# ELRS.net
KiCad netlist of a schematic drawn in Altium Designer
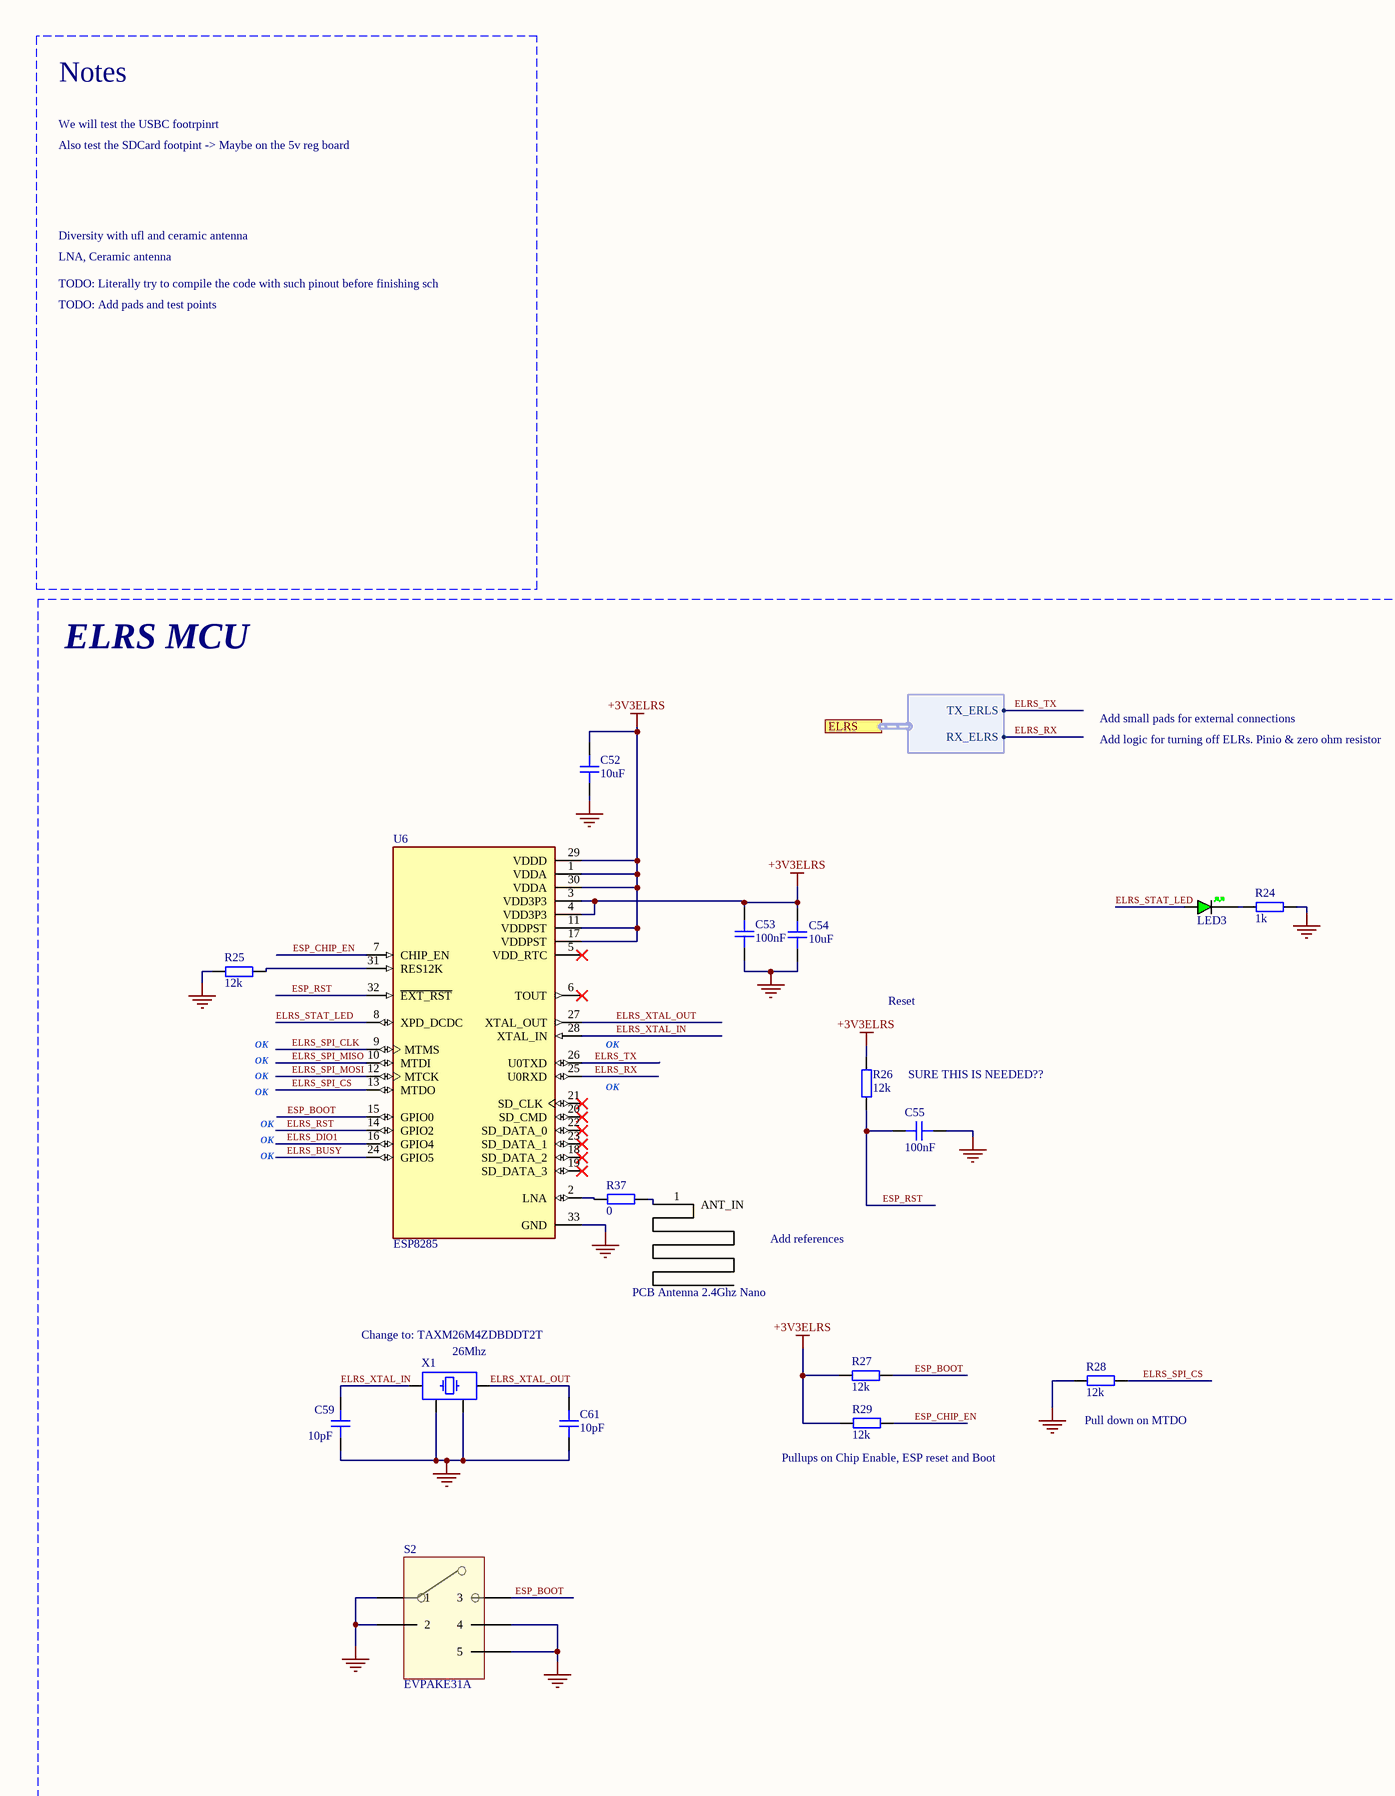
[diagram p0: ELRS.SchDoc, left]
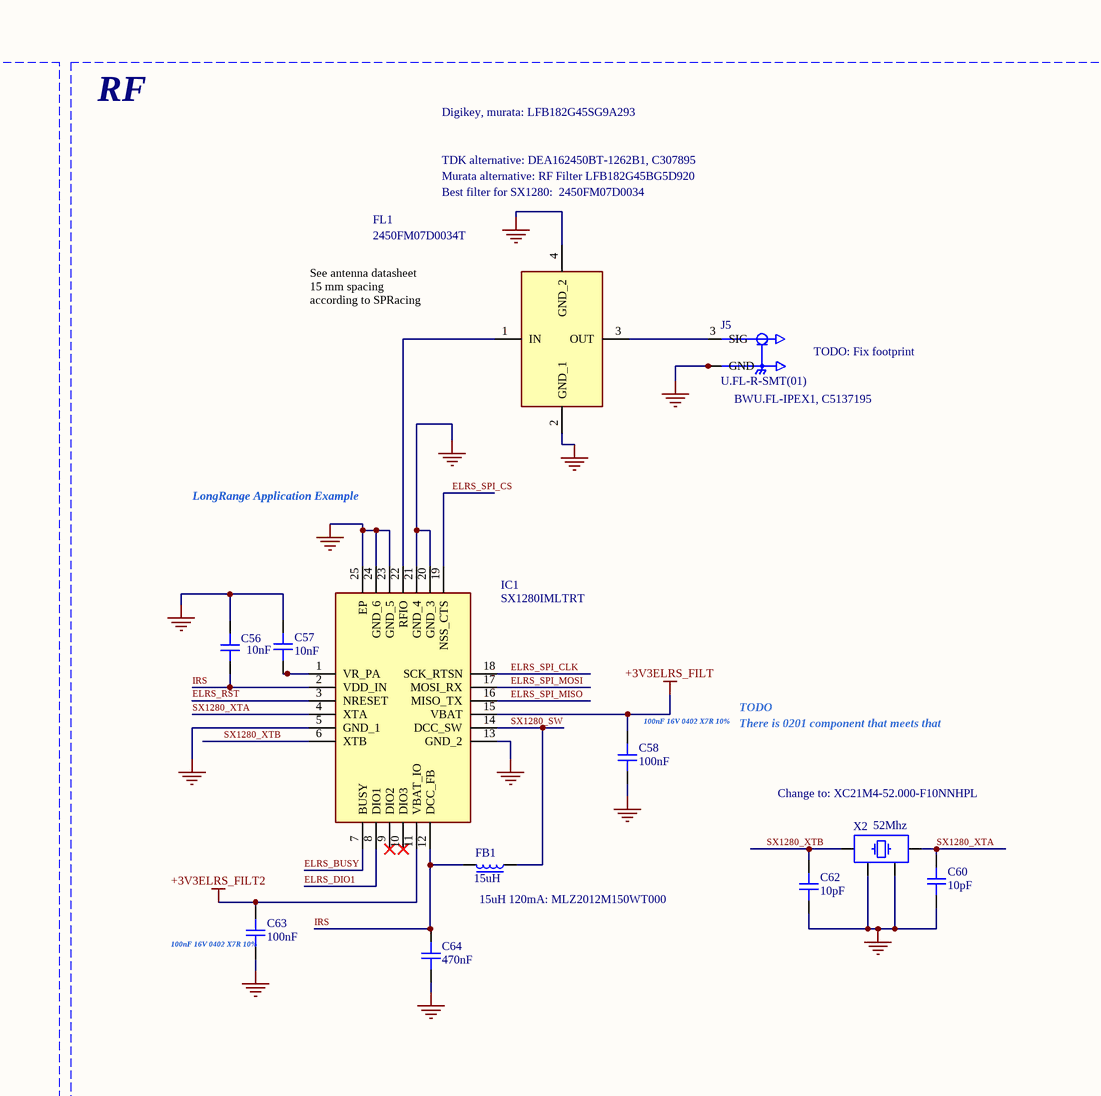
[diagram p1: ELRS.SchDoc, right]

(export (version "E")
  (design (tool "Eeschema 10.0.6"))
  (components
    (comp (ref "C52")
      (value "10uF")
      (footprint "CAP_0402")
      (description "Capacitor SMD 0402")
      (libsource (lib "Schematic-Lib-PhilsLab") (part "CAP_0402"))
    )
    (comp (ref "C53")
      (value "100nF")
      (footprint "CAP_0201")
      (description "Capacitor SMD 0201")
      (libsource (lib "Schematic-Lib-PhilsLab") (part "CAP_0201"))
    )
    (comp (ref "C54")
      (value "10uF")
      (footprint "CAP_0402")
      (description "Capacitor SMD 0402")
      (libsource (lib "Schematic-Lib-PhilsLab") (part "CAP_0402"))
    )
    (comp (ref "C55")
      (value "100nF")
      (footprint "CAP_0201")
      (description "Capacitor SMD 0201")
      (libsource (lib "Schematic-Lib-PhilsLab") (part "CAP_0201"))
    )
    (comp (ref "C56")
      (value "10nF")
      (footprint "CAP_0201")
      (description "Capacitor SMD 0201")
      (libsource (lib "Schematic-Lib-PhilsLab") (part "CAP_0201"))
    )
    (comp (ref "C57")
      (value "10nF")
      (footprint "CAP_0201")
      (description "Capacitor SMD 0201")
      (libsource (lib "Schematic-Lib-PhilsLab") (part "CAP_0201"))
    )
    (comp (ref "C58")
      (value "100nF")
      (footprint "CAP_0201")
      (description "Capacitor SMD 0201")
      (libsource (lib "Schematic-Lib-PhilsLab") (part "CAP_0201"))
    )
    (comp (ref "C59")
      (value "10pF")
      (footprint "CAP_0201")
      (description "Capacitor SMD 0201")
      (libsource (lib "Schematic-Lib-PhilsLab") (part "CAP_0201"))
    )
    (comp (ref "C60")
      (value "10pF")
      (footprint "CAP_0201")
      (description "Capacitor SMD 0201")
      (libsource (lib "Schematic-Lib-PhilsLab") (part "CAP_0201"))
    )
    (comp (ref "C61")
      (value "10pF")
      (footprint "CAP_0201")
      (description "Capacitor SMD 0201")
      (libsource (lib "Schematic-Lib-PhilsLab") (part "CAP_0201"))
    )
    (comp (ref "C62")
      (value "10pF")
      (footprint "CAP_0201")
      (description "Capacitor SMD 0201")
      (libsource (lib "Schematic-Lib-PhilsLab") (part "CAP_0201"))
    )
    (comp (ref "C63")
      (value "100nF")
      (footprint "CAP_0201")
      (description "Capacitor SMD 0201")
      (libsource (lib "Schematic-Lib-PhilsLab") (part "CAP_0201"))
    )
    (comp (ref "C64")
      (value "470nF")
      (footprint "CAP_0402")
      (description "Capacitor SMD 0402")
      (libsource (lib "Schematic-Lib-PhilsLab") (part "CAP_0402"))
    )
    (comp (ref "FB1")
      (value "15uH")
      (footprint "FB_0805")
      (description "Ferrite Bead SMD 0805")
      (libsource (lib "Schematic-Lib-PhilsLab") (part "FB_0805"))
    )
    (comp (ref "FL1")
      (value "2450FM07D0034T")
      (footprint "SamacSys:2450FM07D0034T")
      (description "Filter")
      (fields (field (name "MOUSER PART NUMBER") "609-2450FM07D0034T"))
      (libsource (lib "*") (part "2450FM07D0034T"))
    )
    (comp (ref "IC1")
      (value "SX1280IMLTRT")
      (footprint "SamacSys:QFN50P400X400X100-25N-D")
      (description "Integrated Circuit")
      (fields (field (name "MOUSER PART NUMBER") "947-SX1280IMLTRT"))
      (libsource (lib "*") (part "SX1280IMLTRT"))
    )
    (comp (ref "J5")
      (value "U.FL-R-SMT(01)")
      (footprint "HRS_U.FL-R-SMT(01)")
      (fields (field (name "MF") "Hirose"))
      (libsource (lib "Schematic-Lib-Singu") (part "U.FL-R-SMT(01)"))
    )
    (comp (ref "LED3")
      (value "GREEN")
      (footprint "LED_0402_GREEN")
      (description "LED 0402 GREEN SMD")
      (libsource (lib "Schematic-Lib-PhilsLab") (part "LED_0402_GREEN"))
    )
    (comp (ref "PCNANT1")
      (value "PCB Antenna 2.4Ghz Nano")
      (footprint "PCB Antena Micro 2.4Ghz")
      (libsource (lib "Schematic-Lib-Singu") (part "PCB Antenna 2.4Ghz Nano"))
    )
    (comp (ref "R24")
      (value "1k")
      (footprint "RES_0201")
      (description "Resistor SMD 0201")
      (libsource (lib "Schematic-Lib-PhilsLab") (part "RES_0201"))
    )
    (comp (ref "R25")
      (value "12k")
      (footprint "RES_0201")
      (description "Resistor SMD 0201")
      (libsource (lib "Schematic-Lib-PhilsLab") (part "RES_0201"))
    )
    (comp (ref "R26")
      (value "12k")
      (footprint "RES_0201")
      (description "Resistor SMD 0201")
      (libsource (lib "Schematic-Lib-PhilsLab") (part "RES_0201"))
    )
    (comp (ref "R27")
      (value "12k")
      (footprint "RES_0201")
      (description "Resistor SMD 0201")
      (libsource (lib "Schematic-Lib-PhilsLab") (part "RES_0201"))
    )
    (comp (ref "R28")
      (value "12k")
      (footprint "RES_0201")
      (description "Resistor SMD 0201")
      (libsource (lib "Schematic-Lib-PhilsLab") (part "RES_0201"))
    )
    (comp (ref "R29")
      (value "12k")
      (footprint "RES_0201")
      (description "Resistor SMD 0201")
      (libsource (lib "Schematic-Lib-PhilsLab") (part "RES_0201"))
    )
    (comp (ref "R37")
      (value "0")
      (footprint "RES_0402")
      (description "Resistor SMD 0402")
      (libsource (lib "Schematic-Lib-PhilsLab") (part "RES_0402"))
    )
    (comp (ref "S2")
      (value "EVPAKE31A")
      (footprint "EVPAKE31A")
      (libsource (lib "Schematic-Lib-Singu") (part "EVPAKE31A"))
    )
    (comp (ref "U6")
      (value "ESP8285")
      (footprint "QFN50P500X500X90-33N")
      (description "IC RF TxRx + MCU WiFi 802.11b/g/n 2.4GHz 32-VFQFN Exposed Pad")
      (fields (field (name "MF") "Espressif Systems"))
      (libsource (lib "Schematic-Lib-Singu") (part "ESP8285"))
    )
    (comp (ref "X1")
      (value "26Mhz")
      (footprint "XTAL_2016")
      (description "Crystal SMD 4-Pin 2.0x1.6mm")
      (libsource (lib "Schematic-Lib-PhilsLab") (part "XTAL_2016"))
    )
    (comp (ref "X2")
      (value "52Mhz")
      (footprint "XTAL_2016")
      (description "Crystal SMD 4-Pin 2.0x1.6mm")
      (libsource (lib "Schematic-Lib-PhilsLab") (part "XTAL_2016"))
    )
  )
  (nets
    (net (code "2") (name "+3V3ELRS") (class "Default")
      (node (ref "C52") (pin "2") (pinfunction "2_2") (pintype "passive"))
      (node (ref "C53") (pin "2") (pinfunction "2_2") (pintype "passive"))
      (node (ref "C54") (pin "2") (pinfunction "2_2") (pintype "passive"))
      (node (ref "R26") (pin "2") (pinfunction "2_2") (pintype "passive"))
      (node (ref "R27") (pin "1") (pinfunction "1_1") (pintype "passive"))
      (node (ref "R29") (pin "1") (pinfunction "1_1") (pintype "passive"))
      (node (ref "U6") (pin "1") (pinfunction "VDDA_1") (pintype "power_in"))
      (node (ref "U6") (pin "11") (pinfunction "VDDPST_11") (pintype "power_in"))
      (node (ref "U6") (pin "17") (pinfunction "VDDPST_17") (pintype "power_in"))
      (node (ref "U6") (pin "29") (pinfunction "VDDD_29") (pintype "power_in"))
      (node (ref "U6") (pin "3") (pinfunction "VDD3P3_3") (pintype "power_in"))
      (node (ref "U6") (pin "30") (pinfunction "VDDA_30") (pintype "power_in"))
      (node (ref "U6") (pin "4") (pinfunction "VDD3P3_4") (pintype "power_in"))
    )
    (net (code "3") (name "+3V3ELRS_FILT") (class "Default")
      (node (ref "C58") (pin "2") (pinfunction "2_2") (pintype "passive"))
      (node (ref "IC1") (pin "15") (pinfunction "VBAT_15") (pintype "passive"))
    )
    (net (code "4") (name "+3V3ELRS_FILT2") (class "Default")
      (node (ref "C63") (pin "2") (pinfunction "2_2") (pintype "passive"))
      (node (ref "IC1") (pin "11") (pinfunction "VBAT_IO_11") (pintype "passive"))
    )
    (net (code "5") (name "/ELRS_BUSY") (class "Default")
      (node (ref "IC1") (pin "7") (pinfunction "BUSY_7") (pintype "passive"))
      (node (ref "U6") (pin "24") (pinfunction "GPIO5_24") (pintype "bidirectional"))
    )
    (net (code "6") (name "/ELRS_DIO1") (class "Default")
      (node (ref "IC1") (pin "8") (pinfunction "DIO1_8") (pintype "passive"))
      (node (ref "U6") (pin "16") (pinfunction "GPIO4_16") (pintype "bidirectional"))
    )
    (net (code "7") (name "/ELRS_RST") (class "Default")
      (node (ref "IC1") (pin "3") (pinfunction "NRESET_3") (pintype "passive"))
      (node (ref "U6") (pin "14") (pinfunction "GPIO2_14") (pintype "bidirectional"))
    )
    (net (code "8") (name "/ELRS_RX") (class "Default")
      (node (ref "U6") (pin "25") (pinfunction "U0RXD_25") (pintype "bidirectional"))
    )
    (net (code "9") (name "/ELRS_SPI_CLK") (class "Default")
      (node (ref "IC1") (pin "18") (pinfunction "SCK_RTSN_18") (pintype "passive"))
      (node (ref "U6") (pin "9") (pinfunction "MTMS_9") (pintype "bidirectional"))
    )
    (net (code "10") (name "/ELRS_SPI_CS") (class "Default")
      (node (ref "IC1") (pin "19") (pinfunction "NSS_CTS_19") (pintype "passive"))
      (node (ref "R28") (pin "2") (pinfunction "2_2") (pintype "passive"))
      (node (ref "U6") (pin "13") (pinfunction "MTDO_13") (pintype "bidirectional"))
    )
    (net (code "11") (name "/ELRS_SPI_MISO") (class "Default")
      (node (ref "IC1") (pin "16") (pinfunction "MISO_TX_16") (pintype "passive"))
      (node (ref "U6") (pin "10") (pinfunction "MTDI_10") (pintype "bidirectional"))
    )
    (net (code "12") (name "/ELRS_SPI_MOSI") (class "Default")
      (node (ref "IC1") (pin "17") (pinfunction "MOSI_RX_17") (pintype "passive"))
      (node (ref "U6") (pin "12") (pinfunction "MTCK_12") (pintype "bidirectional"))
    )
    (net (code "13") (name "/ELRS_STAT_LED") (class "Default")
      (node (ref "LED3") (pin "A") (pinfunction "A_A") (pintype "passive"))
      (node (ref "U6") (pin "8") (pinfunction "XPD_DCDC_8") (pintype "bidirectional"))
    )
    (net (code "14") (name "/ELRS_TX") (class "Default")
      (node (ref "U6") (pin "26") (pinfunction "U0TXD_26") (pintype "bidirectional"))
    )
    (net (code "15") (name "/ELRS_XTAL_IN") (class "Default")
      (node (ref "C59") (pin "2") (pinfunction "2_2") (pintype "passive"))
      (node (ref "U6") (pin "28") (pinfunction "XTAL_IN_28") (pintype "input"))
      (node (ref "X1") (pin "1") (pinfunction "1_1") (pintype "passive"))
    )
    (net (code "16") (name "/ELRS_XTAL_OUT") (class "Default")
      (node (ref "C61") (pin "2") (pinfunction "2_2") (pintype "passive"))
      (node (ref "U6") (pin "27") (pinfunction "XTAL_OUT_27") (pintype "output"))
      (node (ref "X1") (pin "3") (pinfunction "3_3") (pintype "passive"))
    )
    (net (code "17") (name "/ESP_BOOT") (class "Default")
      (node (ref "R27") (pin "2") (pinfunction "2_2") (pintype "passive"))
      (node (ref "S2") (pin "3") (pinfunction "3_3") (pintype "passive"))
      (node (ref "U6") (pin "15") (pinfunction "GPIO0_15") (pintype "bidirectional"))
    )
    (net (code "18") (name "/ESP_CHIP_EN") (class "Default")
      (node (ref "R29") (pin "2") (pinfunction "2_2") (pintype "passive"))
      (node (ref "U6") (pin "7") (pinfunction "CHIP_EN_7") (pintype "input"))
    )
    (net (code "19") (name "/ESP_RST") (class "Default")
      (node (ref "C55") (pin "2") (pinfunction "2_2") (pintype "passive"))
      (node (ref "R26") (pin "1") (pinfunction "1_1") (pintype "passive"))
      (node (ref "U6") (pin "32") (pinfunction "~{EXT_RST}_32") (pintype "input"))
    )
    (net (code "20") (name "/IRS") (class "Default")
      (node (ref "C56") (pin "1") (pinfunction "1_1") (pintype "passive"))
      (node (ref "C64") (pin "1") (pinfunction "1_1") (pintype "passive"))
      (node (ref "FB1") (pin "2") (pinfunction "2_2") (pintype "passive"))
      (node (ref "IC1") (pin "12") (pinfunction "DCC_FB_12") (pintype "passive"))
      (node (ref "IC1") (pin "2") (pinfunction "VDD_IN_2") (pintype "passive"))
    )
    (net (code "21") (name "/SX1280_SW") (class "Default")
      (node (ref "FB1") (pin "1") (pinfunction "1_1") (pintype "passive"))
      (node (ref "IC1") (pin "14") (pinfunction "DCC_SW_14") (pintype "passive"))
    )
    (net (code "22") (name "/SX1280_XTA") (class "Default")
      (node (ref "C60") (pin "2") (pinfunction "2_2") (pintype "passive"))
      (node (ref "IC1") (pin "4") (pinfunction "XTA_4") (pintype "passive"))
      (node (ref "X2") (pin "3") (pinfunction "3_3") (pintype "passive"))
    )
    (net (code "23") (name "/SX1280_XTB") (class "Default")
      (node (ref "C62") (pin "2") (pinfunction "2_2") (pintype "passive"))
      (node (ref "IC1") (pin "6") (pinfunction "XTB_6") (pintype "passive"))
      (node (ref "X2") (pin "1") (pinfunction "1_1") (pintype "passive"))
    )
    (net (code "25") (name "GND") (class "Default")
      (node (ref "C52") (pin "1") (pinfunction "1_1") (pintype "passive"))
      (node (ref "C53") (pin "1") (pinfunction "1_1") (pintype "passive"))
      (node (ref "C54") (pin "1") (pinfunction "1_1") (pintype "passive"))
      (node (ref "C55") (pin "1") (pinfunction "1_1") (pintype "passive"))
      (node (ref "C56") (pin "2") (pinfunction "2_2") (pintype "passive"))
      (node (ref "C57") (pin "2") (pinfunction "2_2") (pintype "passive"))
      (node (ref "C58") (pin "1") (pinfunction "1_1") (pintype "passive"))
      (node (ref "C59") (pin "1") (pinfunction "1_1") (pintype "passive"))
      (node (ref "C60") (pin "1") (pinfunction "1_1") (pintype "passive"))
      (node (ref "C61") (pin "1") (pinfunction "1_1") (pintype "passive"))
      (node (ref "C62") (pin "1") (pinfunction "1_1") (pintype "passive"))
      (node (ref "C63") (pin "1") (pinfunction "1_1") (pintype "passive"))
      (node (ref "C64") (pin "2") (pinfunction "2_2") (pintype "passive"))
      (node (ref "FL1") (pin "2") (pinfunction "GND_1_2") (pintype "passive"))
      (node (ref "FL1") (pin "4") (pinfunction "GND_2_4") (pintype "passive"))
      (node (ref "IC1") (pin "13") (pinfunction "GND_2_13") (pintype "passive"))
      (node (ref "IC1") (pin "20") (pinfunction "GND_3_20") (pintype "passive"))
      (node (ref "IC1") (pin "21") (pinfunction "GND_4_21") (pintype "passive"))
      (node (ref "IC1") (pin "23") (pinfunction "GND_5_23") (pintype "passive"))
      (node (ref "IC1") (pin "24") (pinfunction "GND_6_24") (pintype "passive"))
      (node (ref "IC1") (pin "25") (pinfunction "EP_25") (pintype "passive"))
      (node (ref "IC1") (pin "5") (pinfunction "GND_1_5") (pintype "passive"))
      (node (ref "J5") (pin "1") (pinfunction "GND_1") (pintype "passive"))
      (node (ref "J5") (pin "2") (pinfunction "GND_2") (pintype "passive"))
      (node (ref "R24") (pin "2") (pinfunction "2_2") (pintype "passive"))
      (node (ref "R25") (pin "1") (pinfunction "1_1") (pintype "passive"))
      (node (ref "R28") (pin "1") (pinfunction "1_1") (pintype "passive"))
      (node (ref "S2") (pin "1") (pinfunction "1_1") (pintype "passive"))
      (node (ref "S2") (pin "2") (pinfunction "2_2") (pintype "passive"))
      (node (ref "S2") (pin "4") (pinfunction "4_4") (pintype "passive"))
      (node (ref "S2") (pin "5") (pinfunction "5_5") (pintype "passive"))
      (node (ref "U6") (pin "33") (pinfunction "GND_33") (pintype "power_in"))
      (node (ref "X1") (pin "2") (pinfunction "2_2") (pintype "passive"))
      (node (ref "X1") (pin "4") (pinfunction "4_4") (pintype "passive"))
      (node (ref "X2") (pin "2") (pinfunction "2_2") (pintype "passive"))
      (node (ref "X2") (pin "4") (pinfunction "4_4") (pintype "passive"))
    )
    (net (code "26") (name "Net-(FL1-IN)") (class "Default")
      (node (ref "FL1") (pin "1") (pinfunction "IN_1") (pintype "passive"))
      (node (ref "IC1") (pin "22") (pinfunction "RFIO_22") (pintype "passive"))
    )
    (net (code "27") (name "Net-(FL1-OUT)") (class "Default")
      (node (ref "FL1") (pin "3") (pinfunction "OUT_3") (pintype "passive"))
      (node (ref "J5") (pin "3") (pinfunction "SIG_3") (pintype "passive"))
    )
    (net (code "28") (name "Net-(IC1-VR_PA)") (class "Default")
      (node (ref "C57") (pin "1") (pinfunction "1_1") (pintype "passive"))
      (node (ref "IC1") (pin "1") (pinfunction "VR_PA_1") (pintype "passive"))
    )
    (net (code "29") (name "Net-(LED3-PadK)") (class "Default")
      (node (ref "LED3") (pin "K") (pinfunction "K_K") (pintype "passive"))
      (node (ref "R24") (pin "1") (pinfunction "1_1") (pintype "passive"))
    )
    (net (code "30") (name "Net-(PCNANT1-ANT_IN)") (class "Default")
      (node (ref "PCNANT1") (pin "1") (pinfunction "ANT_IN_1") (pintype "passive"))
      (node (ref "R37") (pin "2") (pinfunction "2_2") (pintype "passive"))
    )
    (net (code "31") (name "Net-(U6-LNA)") (class "Default")
      (node (ref "R37") (pin "1") (pinfunction "1_1") (pintype "passive"))
      (node (ref "U6") (pin "2") (pinfunction "LNA_2") (pintype "bidirectional"))
    )
    (net (code "32") (name "Net-(U6-RES12K)") (class "Default")
      (node (ref "R25") (pin "2") (pinfunction "2_2") (pintype "passive"))
      (node (ref "U6") (pin "31") (pinfunction "RES12K_31") (pintype "input"))
    )
    (net (code "33") (name "unconnected-(IC1-DIO2-Pad9)") (class "Default")
      (node (ref "IC1") (pin "9") (pinfunction "DIO2_9") (pintype "passive+no_connect"))
    )
    (net (code "34") (name "unconnected-(IC1-DIO3-Pad10)") (class "Default")
      (node (ref "IC1") (pin "10") (pinfunction "DIO3_10") (pintype "passive+no_connect"))
    )
    (net (code "35") (name "unconnected-(U6-SD_CLK-Pad21)") (class "Default")
      (node (ref "U6") (pin "21") (pinfunction "SD_CLK_21") (pintype "bidirectional+no_connect"))
    )
    (net (code "36") (name "unconnected-(U6-SD_CMD-Pad20)") (class "Default")
      (node (ref "U6") (pin "20") (pinfunction "SD_CMD_20") (pintype "bidirectional+no_connect"))
    )
    (net (code "37") (name "unconnected-(U6-SD_DATA_0-Pad22)") (class "Default")
      (node (ref "U6") (pin "22") (pinfunction "SD_DATA_0_22") (pintype "bidirectional+no_connect"))
    )
    (net (code "38") (name "unconnected-(U6-SD_DATA_1-Pad23)") (class "Default")
      (node (ref "U6") (pin "23") (pinfunction "SD_DATA_1_23") (pintype "bidirectional+no_connect"))
    )
    (net (code "39") (name "unconnected-(U6-SD_DATA_2-Pad18)") (class "Default")
      (node (ref "U6") (pin "18") (pinfunction "SD_DATA_2_18") (pintype "bidirectional+no_connect"))
    )
    (net (code "40") (name "unconnected-(U6-SD_DATA_3-Pad19)") (class "Default")
      (node (ref "U6") (pin "19") (pinfunction "SD_DATA_3_19") (pintype "bidirectional+no_connect"))
    )
    (net (code "41") (name "unconnected-(U6-TOUT-Pad6)") (class "Default")
      (node (ref "U6") (pin "6") (pinfunction "TOUT_6") (pintype "output+no_connect"))
    )
    (net (code "42") (name "unconnected-(U6-VDD_RTC-Pad5)") (class "Default")
      (node (ref "U6") (pin "5") (pinfunction "VDD_RTC_5") (pintype "power_in+no_connect"))
    )
  )
)
